# comparator.net
KiCad netlist of a schematic drawn in Altium Designer
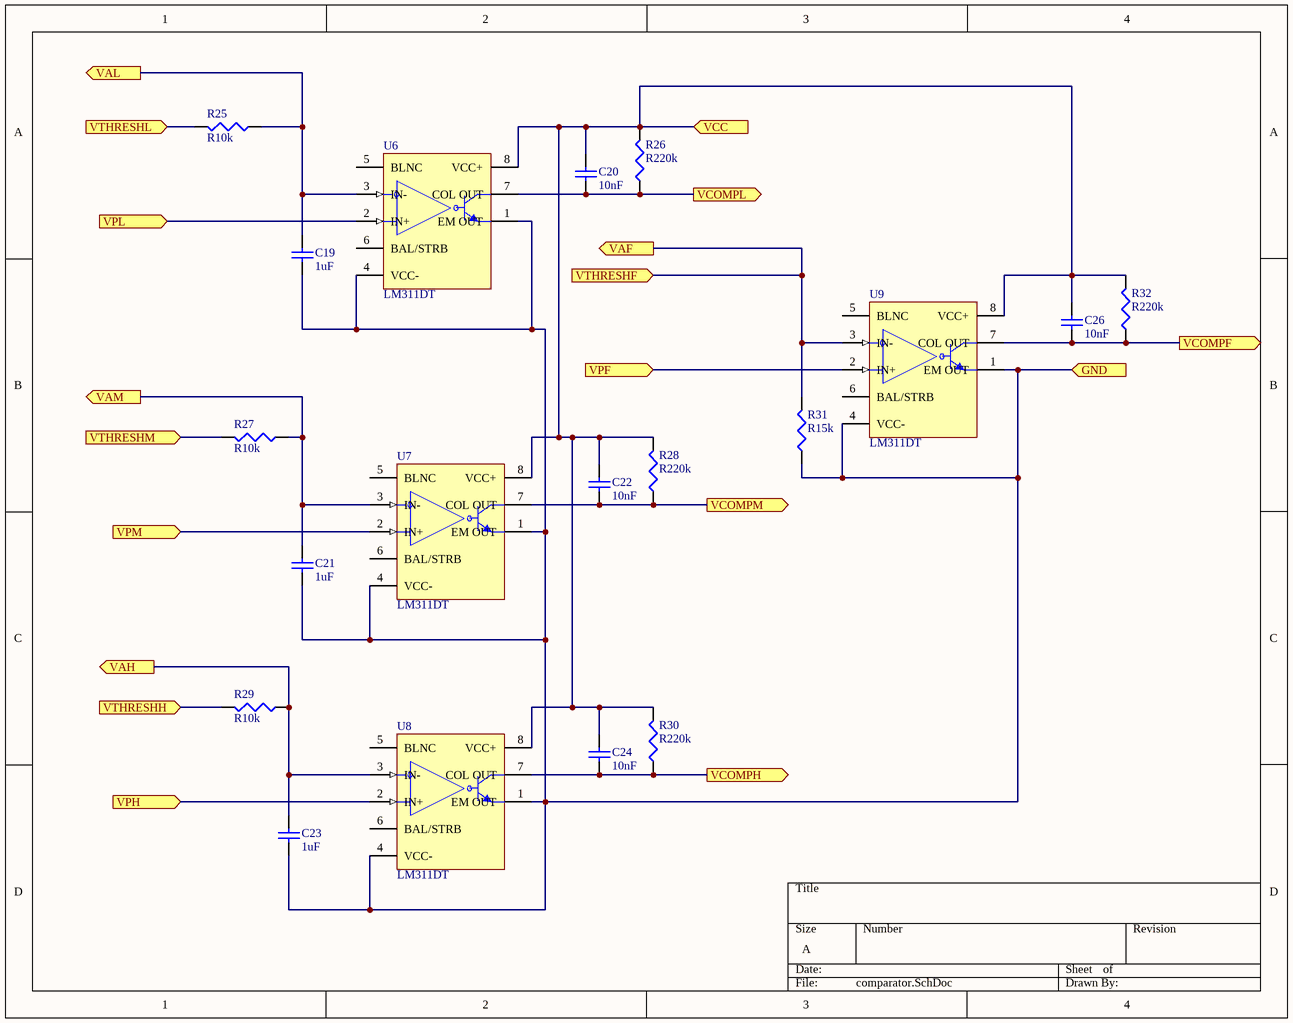
[diagram p0: comparator.SchDoc]

(export (version "E")
  (design (tool "Eeschema 10.0.6"))
  (components
    (comp (ref "C19")
      (value "1uF")
      (footprint "C0603")
      (description "1 uF Surface Mount Capacitor")
      (fields
        (field (name "MANUFACTURER") "Murata Electronics North America")
        (field (name "MANUFACTURER PART NUMBER") "GRM188R61C105KA93D")
      )
      (libsource (lib "Capstone Libraries") (part "C1uF"))
    )
    (comp (ref "C20")
      (value "10nF")
      (footprint "C0603")
      (description "10 nF Surface Mount Capacitor")
      (fields
        (field (name "MANUFACTURER") "Murata Electronics North America")
        (field (name "MANUFACTURER PART NUMBER") "GRM188R70J103KA01D")
      )
      (libsource (lib "Capstone Libraries") (part "C10nF"))
    )
    (comp (ref "C21")
      (value "1uF")
      (footprint "C0603")
      (description "1 uF Surface Mount Capacitor")
      (fields
        (field (name "MANUFACTURER") "Murata Electronics North America")
        (field (name "MANUFACTURER PART NUMBER") "GRM188R61C105KA93D")
      )
      (libsource (lib "Capstone Libraries") (part "C1uF"))
    )
    (comp (ref "C22")
      (value "10nF")
      (footprint "C0603")
      (description "10 nF Surface Mount Capacitor")
      (fields
        (field (name "MANUFACTURER") "Murata Electronics North America")
        (field (name "MANUFACTURER PART NUMBER") "GRM188R70J103KA01D")
      )
      (libsource (lib "Capstone Libraries") (part "C10nF"))
    )
    (comp (ref "C23")
      (value "1uF")
      (footprint "C0603")
      (description "1 uF Surface Mount Capacitor")
      (fields
        (field (name "MANUFACTURER") "Murata Electronics North America")
        (field (name "MANUFACTURER PART NUMBER") "GRM188R61C105KA93D")
      )
      (libsource (lib "Capstone Libraries") (part "C1uF"))
    )
    (comp (ref "C24")
      (value "10nF")
      (footprint "C0603")
      (description "10 nF Surface Mount Capacitor")
      (fields
        (field (name "MANUFACTURER") "Murata Electronics North America")
        (field (name "MANUFACTURER PART NUMBER") "GRM188R70J103KA01D")
      )
      (libsource (lib "Capstone Libraries") (part "C10nF"))
    )
    (comp (ref "C26")
      (value "10nF")
      (footprint "C0603")
      (description "10 nF Surface Mount Capacitor")
      (fields
        (field (name "MANUFACTURER") "Murata Electronics North America")
        (field (name "MANUFACTURER PART NUMBER") "GRM188R70J103KA01D")
      )
      (libsource (lib "Capstone Libraries") (part "C10nF"))
    )
    (comp (ref "R25")
      (value "R10k")
      (footprint "R0603")
      (description "10k Ohms Surface Mount Resistor")
      (fields
        (field (name "MANUFACTURER") "Yageo")
        (field (name "MANUFACTURER PART NUMBER") "RC0603FR-0710KL")
      )
      (libsource (lib "Capstone Libraries") (part "R10k"))
    )
    (comp (ref "R26")
      (value "R220k")
      (footprint "R0603")
      (description "220k Ohms Surface Mount Resistor")
      (fields
        (field (name "MANUFACTURER") "Yageo")
        (field (name "MANUFACTURER PART NUMBER") "RC0603FR-07220KL")
      )
      (libsource (lib "Capstone Libraries") (part "R220k"))
    )
    (comp (ref "R27")
      (value "R10k")
      (footprint "R0603")
      (description "10k Ohms Surface Mount Resistor")
      (fields
        (field (name "MANUFACTURER") "Yageo")
        (field (name "MANUFACTURER PART NUMBER") "RC0603FR-0710KL")
      )
      (libsource (lib "Capstone Libraries") (part "R10k"))
    )
    (comp (ref "R28")
      (value "R220k")
      (footprint "R0603")
      (description "220k Ohms Surface Mount Resistor")
      (fields
        (field (name "MANUFACTURER") "Yageo")
        (field (name "MANUFACTURER PART NUMBER") "RC0603FR-07220KL")
      )
      (libsource (lib "Capstone Libraries") (part "R220k"))
    )
    (comp (ref "R29")
      (value "R10k")
      (footprint "R0603")
      (description "10k Ohms Surface Mount Resistor")
      (fields
        (field (name "MANUFACTURER") "Yageo")
        (field (name "MANUFACTURER PART NUMBER") "RC0603FR-0710KL")
      )
      (libsource (lib "Capstone Libraries") (part "R10k"))
    )
    (comp (ref "R30")
      (value "R220k")
      (footprint "R0603")
      (description "220k Ohms Surface Mount Resistor")
      (fields
        (field (name "MANUFACTURER") "Yageo")
        (field (name "MANUFACTURER PART NUMBER") "RC0603FR-07220KL")
      )
      (libsource (lib "Capstone Libraries") (part "R220k"))
    )
    (comp (ref "R31")
      (value "R15k")
      (footprint "R0603")
      (description "15k Ohms Surface Mount Resistor")
      (fields
        (field (name "MANUFACTURER") "Yageo")
        (field (name "MANUFACTURER PART NUMBER") "RC0603FR-0715KL")
      )
      (libsource (lib "Capstone Libraries") (part "R15k"))
    )
    (comp (ref "R32")
      (value "R220k")
      (footprint "R0603")
      (description "220k Ohms Surface Mount Resistor")
      (fields
        (field (name "MANUFACTURER") "Yageo")
        (field (name "MANUFACTURER PART NUMBER") "RC0603FR-07220KL")
      )
      (libsource (lib "Capstone Libraries") (part "R220k"))
    )
    (comp (ref "U6")
      (value "LM311DT")
      (footprint "soic8")
      (description "IC Comparator")
      (fields (field (name "MANUFACTURER") "STMicroelectronics"))
      (libsource (lib "Capstone Libraries") (part "LM311DT"))
    )
    (comp (ref "U7")
      (value "LM311DT")
      (footprint "soic8")
      (description "IC Comparator")
      (fields (field (name "MANUFACTURER") "STMicroelectronics"))
      (libsource (lib "Capstone Libraries") (part "LM311DT"))
    )
    (comp (ref "U8")
      (value "LM311DT")
      (footprint "soic8")
      (description "IC Comparator")
      (fields (field (name "MANUFACTURER") "STMicroelectronics"))
      (libsource (lib "Capstone Libraries") (part "LM311DT"))
    )
    (comp (ref "U9")
      (value "LM311DT")
      (footprint "soic8")
      (description "IC Comparator")
      (fields (field (name "MANUFACTURER") "STMicroelectronics"))
      (libsource (lib "Capstone Libraries") (part "LM311DT"))
    )
  )
  (nets
    (net (code "1") (name "/GND") (class "Default")
      (node (ref "C19") (pin "2") (pinfunction "2_2") (pintype "passive"))
      (node (ref "C21") (pin "2") (pinfunction "2_2") (pintype "passive"))
      (node (ref "C23") (pin "2") (pinfunction "2_2") (pintype "passive"))
      (node (ref "R31") (pin "1") (pinfunction "1_1") (pintype "passive"))
      (node (ref "U6") (pin "1") (pinfunction "EM_OUT_1") (pintype "passive"))
      (node (ref "U6") (pin "4") (pinfunction "VCC-_4") (pintype "passive"))
      (node (ref "U7") (pin "1") (pinfunction "EM_OUT_1") (pintype "passive"))
      (node (ref "U7") (pin "4") (pinfunction "VCC-_4") (pintype "passive"))
      (node (ref "U8") (pin "1") (pinfunction "EM_OUT_1") (pintype "passive"))
      (node (ref "U8") (pin "4") (pinfunction "VCC-_4") (pintype "passive"))
      (node (ref "U9") (pin "1") (pinfunction "EM_OUT_1") (pintype "passive"))
      (node (ref "U9") (pin "4") (pinfunction "VCC-_4") (pintype "passive"))
    )
    (net (code "2") (name "/VAF") (class "Default")
      (node (ref "R31") (pin "2") (pinfunction "2_2") (pintype "passive"))
      (node (ref "U9") (pin "3") (pinfunction "IN-_3") (pintype "input"))
    )
    (net (code "3") (name "/VAH") (class "Default")
      (node (ref "C23") (pin "1") (pinfunction "1_1") (pintype "passive"))
      (node (ref "R29") (pin "1") (pinfunction "1_1") (pintype "passive"))
      (node (ref "U8") (pin "3") (pinfunction "IN-_3") (pintype "input"))
    )
    (net (code "4") (name "/VAL") (class "Default")
      (node (ref "C19") (pin "1") (pinfunction "1_1") (pintype "passive"))
      (node (ref "R25") (pin "1") (pinfunction "1_1") (pintype "passive"))
      (node (ref "U6") (pin "3") (pinfunction "IN-_3") (pintype "input"))
    )
    (net (code "5") (name "/VAM") (class "Default")
      (node (ref "C21") (pin "1") (pinfunction "1_1") (pintype "passive"))
      (node (ref "R27") (pin "1") (pinfunction "1_1") (pintype "passive"))
      (node (ref "U7") (pin "3") (pinfunction "IN-_3") (pintype "input"))
    )
    (net (code "6") (name "/VCC") (class "Default")
      (node (ref "C20") (pin "1") (pinfunction "1_1") (pintype "passive"))
      (node (ref "C22") (pin "1") (pinfunction "1_1") (pintype "passive"))
      (node (ref "C24") (pin "1") (pinfunction "1_1") (pintype "passive"))
      (node (ref "C26") (pin "1") (pinfunction "1_1") (pintype "passive"))
      (node (ref "R26") (pin "2") (pinfunction "2_2") (pintype "passive"))
      (node (ref "R28") (pin "2") (pinfunction "2_2") (pintype "passive"))
      (node (ref "R30") (pin "2") (pinfunction "2_2") (pintype "passive"))
      (node (ref "R32") (pin "2") (pinfunction "2_2") (pintype "passive"))
      (node (ref "U6") (pin "8") (pinfunction "VCC+_8") (pintype "passive"))
      (node (ref "U7") (pin "8") (pinfunction "VCC+_8") (pintype "passive"))
      (node (ref "U8") (pin "8") (pinfunction "VCC+_8") (pintype "passive"))
      (node (ref "U9") (pin "8") (pinfunction "VCC+_8") (pintype "passive"))
    )
    (net (code "7") (name "/VCOMPF") (class "Default")
      (node (ref "C26") (pin "2") (pinfunction "2_2") (pintype "passive"))
      (node (ref "R32") (pin "1") (pinfunction "1_1") (pintype "passive"))
      (node (ref "U9") (pin "7") (pinfunction "COL_OUT_7") (pintype "passive"))
    )
    (net (code "8") (name "/VCOMPH") (class "Default")
      (node (ref "C24") (pin "2") (pinfunction "2_2") (pintype "passive"))
      (node (ref "R30") (pin "1") (pinfunction "1_1") (pintype "passive"))
      (node (ref "U8") (pin "7") (pinfunction "COL_OUT_7") (pintype "passive"))
    )
    (net (code "9") (name "/VCOMPL") (class "Default")
      (node (ref "C20") (pin "2") (pinfunction "2_2") (pintype "passive"))
      (node (ref "R26") (pin "1") (pinfunction "1_1") (pintype "passive"))
      (node (ref "U6") (pin "7") (pinfunction "COL_OUT_7") (pintype "passive"))
    )
    (net (code "10") (name "/VCOMPM") (class "Default")
      (node (ref "C22") (pin "2") (pinfunction "2_2") (pintype "passive"))
      (node (ref "R28") (pin "1") (pinfunction "1_1") (pintype "passive"))
      (node (ref "U7") (pin "7") (pinfunction "COL_OUT_7") (pintype "passive"))
    )
    (net (code "11") (name "/VPF") (class "Default")
      (node (ref "U9") (pin "2") (pinfunction "IN+_2") (pintype "input"))
    )
    (net (code "12") (name "/VPH") (class "Default")
      (node (ref "U8") (pin "2") (pinfunction "IN+_2") (pintype "input"))
    )
    (net (code "13") (name "/VPL") (class "Default")
      (node (ref "U6") (pin "2") (pinfunction "IN+_2") (pintype "input"))
    )
    (net (code "14") (name "/VPM") (class "Default")
      (node (ref "U7") (pin "2") (pinfunction "IN+_2") (pintype "input"))
    )
    (net (code "15") (name "/VTHRESHH") (class "Default")
      (node (ref "R29") (pin "2") (pinfunction "2_2") (pintype "passive"))
    )
    (net (code "16") (name "/VTHRESHL") (class "Default")
      (node (ref "R25") (pin "2") (pinfunction "2_2") (pintype "passive"))
    )
    (net (code "17") (name "/VTHRESHM") (class "Default")
      (node (ref "R27") (pin "2") (pinfunction "2_2") (pintype "passive"))
    )
    (net (code "18") (name "unconnected-(U6-BAL{slash}STRB-Pad6)") (class "Default")
      (node (ref "U6") (pin "6") (pinfunction "BAL/STRB_6") (pintype "passive"))
    )
    (net (code "19") (name "unconnected-(U6-BLNC-Pad5)") (class "Default")
      (node (ref "U6") (pin "5") (pinfunction "BLNC_5") (pintype "passive"))
    )
    (net (code "20") (name "unconnected-(U7-BAL{slash}STRB-Pad6)") (class "Default")
      (node (ref "U7") (pin "6") (pinfunction "BAL/STRB_6") (pintype "passive"))
    )
    (net (code "21") (name "unconnected-(U7-BLNC-Pad5)") (class "Default")
      (node (ref "U7") (pin "5") (pinfunction "BLNC_5") (pintype "passive"))
    )
    (net (code "22") (name "unconnected-(U8-BAL{slash}STRB-Pad6)") (class "Default")
      (node (ref "U8") (pin "6") (pinfunction "BAL/STRB_6") (pintype "passive"))
    )
    (net (code "23") (name "unconnected-(U8-BLNC-Pad5)") (class "Default")
      (node (ref "U8") (pin "5") (pinfunction "BLNC_5") (pintype "passive"))
    )
    (net (code "24") (name "unconnected-(U9-BAL{slash}STRB-Pad6)") (class "Default")
      (node (ref "U9") (pin "6") (pinfunction "BAL/STRB_6") (pintype "passive"))
    )
    (net (code "25") (name "unconnected-(U9-BLNC-Pad5)") (class "Default")
      (node (ref "U9") (pin "5") (pinfunction "BLNC_5") (pintype "passive"))
    )
  )
)
